# v0.net
KiCad netlist of a schematic drawn in Altium Designer
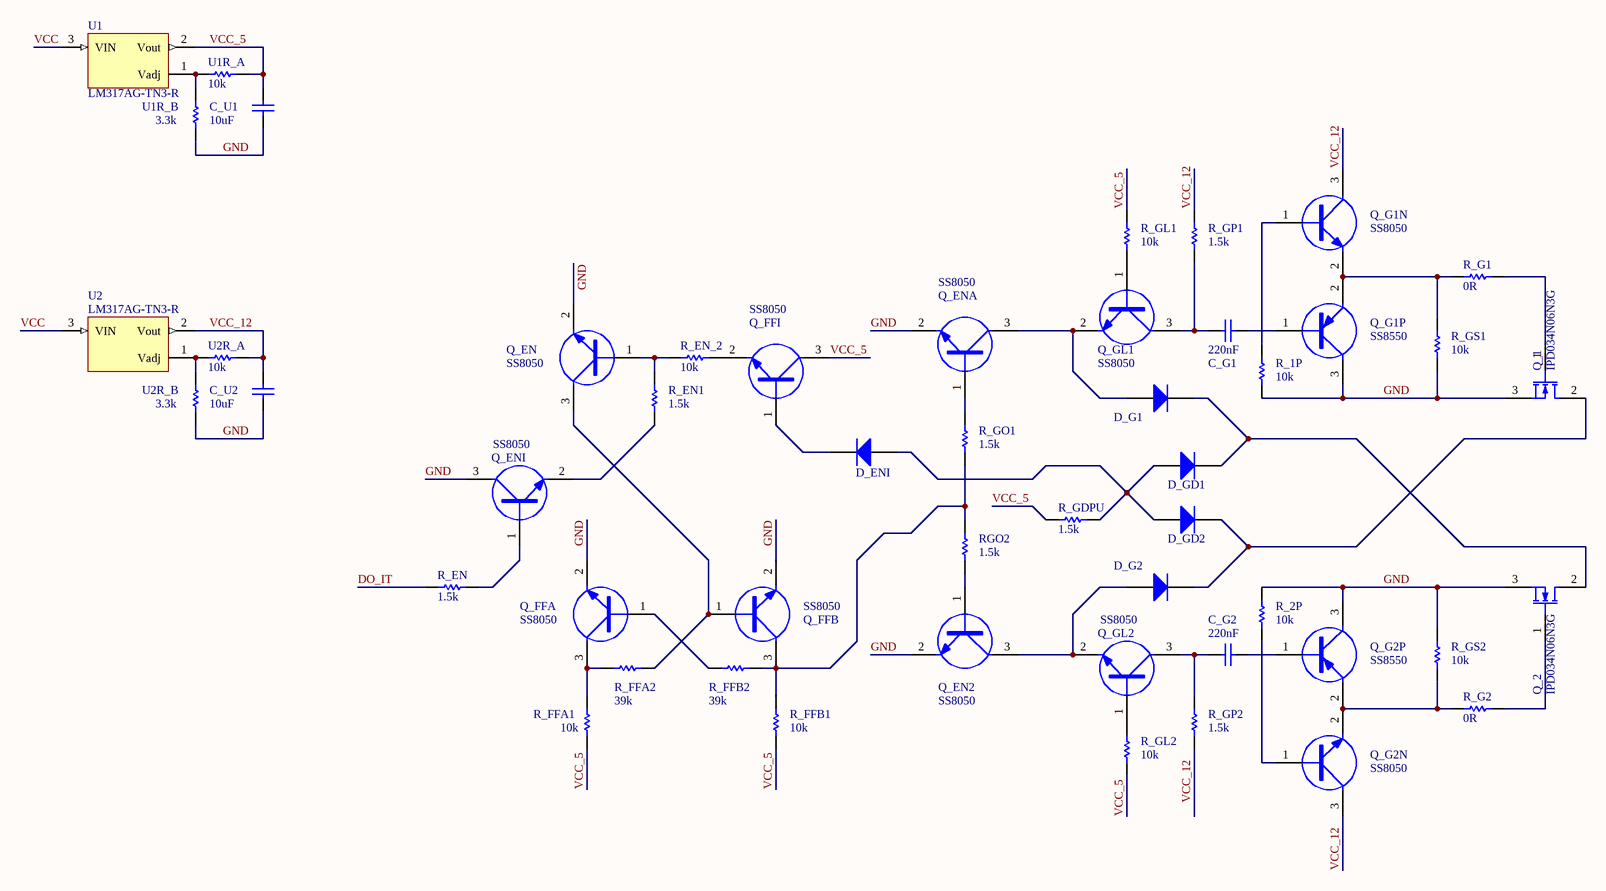
[diagram p0: v0.SchDoc]

(export (version "E")
  (design (tool "Eeschema 10.0.6"))
  (components
    (comp (ref "C_G1")
      (value "220nF")
      (footprint "CAP 0402")
      (description "CAPACITOR MLCC - 220nF 16V 0402")
      (fields (field (name "LCSC PART #") "C16772") (field (name "Comment") "CL05B224KO5NNNC"))
      (libsource (lib "JLC_PCB") (part "CL05B224KO5NNNC"))
    )
    (comp (ref "C_G2")
      (value "220nF")
      (footprint "CAP 0402")
      (description "CAPACITOR MLCC - 220nF 16V 0402")
      (fields (field (name "LCSC PART #") "C16772") (field (name "Comment") "CL05B224KO5NNNC"))
      (libsource (lib "JLC_PCB") (part "CL05B224KO5NNNC"))
    )
    (comp (ref "C_U1")
      (value "10uF")
      (footprint "CAP 0805")
      (description "CAPACITOR MLCC - 10uF 25V 0805")
      (fields (field (name "LCSC PART #") "C15850") (field (name "Comment") "CL21A106KAYNNNE"))
      (libsource (lib "JLC_PCB") (part "CL21A106KAYNNNE"))
    )
    (comp (ref "C_U2")
      (value "10uF")
      (footprint "CAP 0805")
      (description "CAPACITOR MLCC - 10uF 25V 0805")
      (fields (field (name "LCSC PART #") "C15850") (field (name "Comment") "CL21A106KAYNNNE"))
      (libsource (lib "JLC_PCB") (part "CL21A106KAYNNNE"))
    )
    (comp (ref "D_ENI")
      (value "N4148WS")
      (footprint "sod-323")
      (description "DIODE - 100V 150MA 1.25V @ 150MA 4NS SOD-323")
      (fields (field (name "LCSC PART #") "C2128"))
      (libsource (lib "JLC_PCB") (part "N4148WS"))
    )
    (comp (ref "D_G1")
      (value "N4148WS")
      (footprint "sod-323")
      (description "DIODE - 100V 150MA 1.25V @ 150MA 4NS SOD-323")
      (fields (field (name "LCSC PART #") "C2128"))
      (libsource (lib "JLC_PCB") (part "N4148WS"))
    )
    (comp (ref "D_G2")
      (value "N4148WS")
      (footprint "sod-323")
      (description "DIODE - 100V 150MA 1.25V @ 150MA 4NS SOD-323")
      (fields (field (name "LCSC PART #") "C2128"))
      (libsource (lib "JLC_PCB") (part "N4148WS"))
    )
    (comp (ref "D_GD1")
      (value "N4148WS")
      (footprint "sod-323")
      (description "DIODE - 100V 150MA 1.25V @ 150MA 4NS SOD-323")
      (fields (field (name "LCSC PART #") "C2128"))
      (libsource (lib "JLC_PCB") (part "N4148WS"))
    )
    (comp (ref "D_GD2")
      (value "N4148WS")
      (footprint "sod-323")
      (description "DIODE - 100V 150MA 1.25V @ 150MA 4NS SOD-323")
      (fields (field (name "LCSC PART #") "C2128"))
      (libsource (lib "JLC_PCB") (part "N4148WS"))
    )
    (comp (ref "Q_1")
      (value "IPD034N06N3G")
      (footprint "to-252-2")
      (description "MOSFET (N) - TRENCH 60V 100A 4V @ 93UA 3.4 M? @ 100A,10V TO-252-2(DPAK) ROHS")
      (fields (field (name "LCSC PART #") "C94897"))
      (libsource (lib "JLC_PCB") (part "IPD034N06N3G"))
    )
    (comp (ref "Q_2")
      (value "IPD034N06N3G")
      (footprint "to-252-2")
      (description "MOSFET (N) - TRENCH 60V 100A 4V @ 93UA 3.4 M? @ 100A,10V TO-252-2(DPAK) ROHS")
      (fields (field (name "LCSC PART #") "C94897"))
      (libsource (lib "JLC_PCB") (part "IPD034N06N3G"))
    )
    (comp (ref "Q_EN")
      (value "SS8050")
      (footprint "SOT-23-3")
      (description "BJT NPN - 25V 1.5A")
      (fields (field (name "LCSC PART #") "C2150"))
      (libsource (lib "JLC_PCB") (part "SS8050"))
    )
    (comp (ref "Q_EN2")
      (value "SS8050")
      (footprint "SOT-23-3")
      (description "BJT NPN - 25V 1.5A")
      (fields (field (name "LCSC PART #") "C2150"))
      (libsource (lib "JLC_PCB") (part "SS8050"))
    )
    (comp (ref "Q_ENA")
      (value "SS8050")
      (footprint "SOT-23-3")
      (description "BJT NPN - 25V 1.5A")
      (fields (field (name "LCSC PART #") "C2150"))
      (libsource (lib "JLC_PCB") (part "SS8050"))
    )
    (comp (ref "Q_ENI")
      (value "SS8050")
      (footprint "SOT-23-3")
      (description "BJT NPN - 25V 1.5A")
      (fields (field (name "LCSC PART #") "C2150"))
      (libsource (lib "JLC_PCB") (part "SS8050"))
    )
    (comp (ref "Q_FFA")
      (value "SS8050")
      (footprint "SOT-23-3")
      (description "BJT NPN - 25V 1.5A")
      (fields (field (name "LCSC PART #") "C2150"))
      (libsource (lib "JLC_PCB") (part "SS8050"))
    )
    (comp (ref "Q_FFB")
      (value "SS8050")
      (footprint "SOT-23-3")
      (description "BJT NPN - 25V 1.5A")
      (fields (field (name "LCSC PART #") "C2150"))
      (libsource (lib "JLC_PCB") (part "SS8050"))
    )
    (comp (ref "Q_FFI")
      (value "SS8050")
      (footprint "SOT-23-3")
      (description "BJT NPN - 25V 1.5A")
      (fields (field (name "LCSC PART #") "C2150"))
      (libsource (lib "JLC_PCB") (part "SS8050"))
    )
    (comp (ref "Q_G1N")
      (value "SS8050")
      (footprint "SOT-23-3")
      (description "BJT NPN - 25V 1.5A")
      (fields (field (name "LCSC PART #") "C2150"))
      (libsource (lib "JLC_PCB") (part "SS8050"))
    )
    (comp (ref "Q_G1P")
      (value "SS8550")
      (footprint "SOT-23-3")
      (description "BJT PNP - 25V 1.5A")
      (fields (field (name "LCSC PART #") "C8542"))
      (libsource (lib "JLC_PCB") (part "SS8550"))
    )
    (comp (ref "Q_G2N")
      (value "SS8050")
      (footprint "SOT-23-3")
      (description "BJT NPN - 25V 1.5A")
      (fields (field (name "LCSC PART #") "C2150"))
      (libsource (lib "JLC_PCB") (part "SS8050"))
    )
    (comp (ref "Q_G2P")
      (value "SS8550")
      (footprint "SOT-23-3")
      (description "BJT PNP - 25V 1.5A")
      (fields (field (name "LCSC PART #") "C8542"))
      (libsource (lib "JLC_PCB") (part "SS8550"))
    )
    (comp (ref "Q_GL1")
      (value "SS8050")
      (footprint "SOT-23-3")
      (description "BJT NPN - 25V 1.5A")
      (fields (field (name "LCSC PART #") "C2150"))
      (libsource (lib "JLC_PCB") (part "SS8050"))
    )
    (comp (ref "Q_GL2")
      (value "SS8050")
      (footprint "SOT-23-3")
      (description "BJT NPN - 25V 1.5A")
      (fields (field (name "LCSC PART #") "C2150"))
      (libsource (lib "JLC_PCB") (part "SS8050"))
    )
    (comp (ref "RGO2")
      (value "1.5k")
      (footprint "RES 0402")
      (description "RESISTOR SMD - 1.5k 1% 0402")
      (fields (field (name "LCSC PART #") "C25867") (field (name "Comment") "0402WGF1501TCE"))
      (libsource (lib "JLC_PCB") (part "0402WGF1501TCE"))
    )
    (comp (ref "R_1P")
      (value "10k")
      (footprint "RES 0402")
      (description "RESISTOR SMD - 10k 1% 0402")
      (fields (field (name "LCSC PART #") "C25744") (field (name "Comment") "0402WGF1002TCE"))
      (libsource (lib "JLC_PCB") (part "0402WGF1002TCE"))
    )
    (comp (ref "R_2P")
      (value "10k")
      (footprint "RES 0402")
      (description "RESISTOR SMD - 10k 1% 0402")
      (fields (field (name "LCSC PART #") "C25744") (field (name "Comment") "0402WGF1002TCE"))
      (libsource (lib "JLC_PCB") (part "0402WGF1002TCE"))
    )
    (comp (ref "R_EN")
      (value "1.5k")
      (footprint "RES 0402")
      (description "RESISTOR SMD - 1.5k 1% 0402")
      (fields (field (name "LCSC PART #") "C25867") (field (name "Comment") "0402WGF1501TCE"))
      (libsource (lib "JLC_PCB") (part "0402WGF1501TCE"))
    )
    (comp (ref "R_EN1")
      (value "1.5k")
      (footprint "RES 0402")
      (description "RESISTOR SMD - 1.5k 1% 0402")
      (fields (field (name "LCSC PART #") "C25867") (field (name "Comment") "0402WGF1501TCE"))
      (libsource (lib "JLC_PCB") (part "0402WGF1501TCE"))
    )
    (comp (ref "R_EN_2")
      (value "10k")
      (footprint "RES 0402")
      (description "RESISTOR SMD - 10k 1% 0402")
      (fields (field (name "LCSC PART #") "C25744") (field (name "Comment") "0402WGF1002TCE"))
      (libsource (lib "JLC_PCB") (part "0402WGF1002TCE"))
    )
    (comp (ref "R_FFA1")
      (value "10k")
      (footprint "RES 0402")
      (description "RESISTOR SMD - 10k 1% 0402")
      (fields (field (name "LCSC PART #") "C25744") (field (name "Comment") "0402WGF1002TCE"))
      (libsource (lib "JLC_PCB") (part "0402WGF1002TCE"))
    )
    (comp (ref "R_FFA2")
      (value "39k")
      (footprint "RES 0402")
      (description "RESISTOR SMD - 39k 1% 0402")
      (fields (field (name "LCSC PART #") "C25783") (field (name "Comment") "0402WGF3902TCE"))
      (libsource (lib "JLC_PCB") (part "0402WGF3902TCE"))
    )
    (comp (ref "R_FFB1")
      (value "10k")
      (footprint "RES 0402")
      (description "RESISTOR SMD - 10k 1% 0402")
      (fields (field (name "LCSC PART #") "C25744") (field (name "Comment") "0402WGF1002TCE"))
      (libsource (lib "JLC_PCB") (part "0402WGF1002TCE"))
    )
    (comp (ref "R_FFB2")
      (value "39k")
      (footprint "RES 0402")
      (description "RESISTOR SMD - 39k 1% 0402")
      (fields (field (name "LCSC PART #") "C25783") (field (name "Comment") "0402WGF3902TCE"))
      (libsource (lib "JLC_PCB") (part "0402WGF3902TCE"))
    )
    (comp (ref "R_G1")
      (value "0R")
      (footprint "RES 0402")
      (description "RESISTOR SMD - 0R 1% 0402")
      (fields (field (name "LCSC PART #") "C17168") (field (name "Comment") "0402WGF0000TCE"))
      (libsource (lib "JLC_PCB") (part "0402WGF0000TCE"))
    )
    (comp (ref "R_G2")
      (value "0R")
      (footprint "RES 0402")
      (description "RESISTOR SMD - 0R 1% 0402")
      (fields (field (name "LCSC PART #") "C17168") (field (name "Comment") "0402WGF0000TCE"))
      (libsource (lib "JLC_PCB") (part "0402WGF0000TCE"))
    )
    (comp (ref "R_GDPU")
      (value "1.5k")
      (footprint "RES 0402")
      (description "RESISTOR SMD - 1.5k 1% 0402")
      (fields (field (name "LCSC PART #") "C25867") (field (name "Comment") "0402WGF1501TCE"))
      (libsource (lib "JLC_PCB") (part "0402WGF1501TCE"))
    )
    (comp (ref "R_GL1")
      (value "10k")
      (footprint "RES 0402")
      (description "RESISTOR SMD - 10k 1% 0402")
      (fields (field (name "LCSC PART #") "C25744") (field (name "Comment") "0402WGF1002TCE"))
      (libsource (lib "JLC_PCB") (part "0402WGF1002TCE"))
    )
    (comp (ref "R_GL2")
      (value "10k")
      (footprint "RES 0402")
      (description "RESISTOR SMD - 10k 1% 0402")
      (fields (field (name "LCSC PART #") "C25744") (field (name "Comment") "0402WGF1002TCE"))
      (libsource (lib "JLC_PCB") (part "0402WGF1002TCE"))
    )
    (comp (ref "R_GO1")
      (value "1.5k")
      (footprint "RES 0402")
      (description "RESISTOR SMD - 1.5k 1% 0402")
      (fields (field (name "LCSC PART #") "C25867") (field (name "Comment") "0402WGF1501TCE"))
      (libsource (lib "JLC_PCB") (part "0402WGF1501TCE"))
    )
    (comp (ref "R_GP1")
      (value "1.5k")
      (footprint "RES 0402")
      (description "RESISTOR SMD - 1.5k 1% 0402")
      (fields (field (name "LCSC PART #") "C25867") (field (name "Comment") "0402WGF1501TCE"))
      (libsource (lib "JLC_PCB") (part "0402WGF1501TCE"))
    )
    (comp (ref "R_GP2")
      (value "1.5k")
      (footprint "RES 0402")
      (description "RESISTOR SMD - 1.5k 1% 0402")
      (fields (field (name "LCSC PART #") "C25867") (field (name "Comment") "0402WGF1501TCE"))
      (libsource (lib "JLC_PCB") (part "0402WGF1501TCE"))
    )
    (comp (ref "R_GS1")
      (value "10k")
      (footprint "RES 0402")
      (description "RESISTOR SMD - 10k 1% 0402")
      (fields (field (name "LCSC PART #") "C25744") (field (name "Comment") "0402WGF1002TCE"))
      (libsource (lib "JLC_PCB") (part "0402WGF1002TCE"))
    )
    (comp (ref "R_GS2")
      (value "10k")
      (footprint "RES 0402")
      (description "RESISTOR SMD - 10k 1% 0402")
      (fields (field (name "LCSC PART #") "C25744") (field (name "Comment") "0402WGF1002TCE"))
      (libsource (lib "JLC_PCB") (part "0402WGF1002TCE"))
    )
    (comp (ref "U1")
      (value "LM317AG-TN3-R")
      (footprint "TO-252-2")
      (description "IC - LDO")
      (fields (field (name "LCSC PART #") "C75510"))
      (libsource (lib "JLC_PCB") (part "LM317AG-TN3-R"))
    )
    (comp (ref "U1R_A")
      (value "10k")
      (footprint "RES 0402")
      (description "RESISTOR SMD - 10k 1% 0402")
      (fields (field (name "LCSC PART #") "C25744") (field (name "Comment") "0402WGF1002TCE"))
      (libsource (lib "JLC_PCB") (part "0402WGF1002TCE"))
    )
    (comp (ref "U1R_B")
      (value "3.3k")
      (footprint "RES 0402")
      (description "RESISTOR SMD - 3.3k 1% 0402")
      (fields (field (name "LCSC PART #") "C25890") (field (name "Comment") "0402WGF3301TCE"))
      (libsource (lib "JLC_PCB") (part "0402WGF3301TCE"))
    )
    (comp (ref "U2")
      (value "LM317AG-TN3-R")
      (footprint "TO-252-2")
      (description "IC - LDO")
      (fields (field (name "LCSC PART #") "C75510"))
      (libsource (lib "JLC_PCB") (part "LM317AG-TN3-R"))
    )
    (comp (ref "U2R_A")
      (value "10k")
      (footprint "RES 0402")
      (description "RESISTOR SMD - 10k 1% 0402")
      (fields (field (name "LCSC PART #") "C25744") (field (name "Comment") "0402WGF1002TCE"))
      (libsource (lib "JLC_PCB") (part "0402WGF1002TCE"))
    )
    (comp (ref "U2R_B")
      (value "3.3k")
      (footprint "RES 0402")
      (description "RESISTOR SMD - 3.3k 1% 0402")
      (fields (field (name "LCSC PART #") "C25890") (field (name "Comment") "0402WGF3301TCE"))
      (libsource (lib "JLC_PCB") (part "0402WGF3301TCE"))
    )
  )
  (nets
    (net (code "1") (name "/DO_IT") (class "Default")
      (node (ref "R_EN") (pin "2") (pinfunction "2_2") (pintype "passive"))
    )
    (net (code "2") (name "/GND") (class "Default")
      (node (ref "C_U1") (pin "1") (pinfunction "1_1") (pintype "passive"))
      (node (ref "C_U2") (pin "1") (pinfunction "1_1") (pintype "passive"))
      (node (ref "Q_1") (pin "3") (pinfunction "S_3") (pintype "passive"))
      (node (ref "Q_2") (pin "3") (pinfunction "S_3") (pintype "passive"))
      (node (ref "Q_EN") (pin "2") (pinfunction "E_2") (pintype "passive"))
      (node (ref "Q_EN2") (pin "2") (pinfunction "E_2") (pintype "passive"))
      (node (ref "Q_ENA") (pin "2") (pinfunction "E_2") (pintype "passive"))
      (node (ref "Q_ENI") (pin "3") (pinfunction "C_3") (pintype "passive"))
      (node (ref "Q_FFA") (pin "2") (pinfunction "E_2") (pintype "passive"))
      (node (ref "Q_FFB") (pin "2") (pinfunction "E_2") (pintype "passive"))
      (node (ref "Q_G1P") (pin "3") (pinfunction "C_3") (pintype "passive"))
      (node (ref "Q_G2P") (pin "3") (pinfunction "C_3") (pintype "passive"))
      (node (ref "R_1P") (pin "1") (pinfunction "1_1") (pintype "passive"))
      (node (ref "R_2P") (pin "2") (pinfunction "2_2") (pintype "passive"))
      (node (ref "R_GS1") (pin "1") (pinfunction "1_1") (pintype "passive"))
      (node (ref "R_GS2") (pin "2") (pinfunction "2_2") (pintype "passive"))
      (node (ref "U1R_B") (pin "1") (pinfunction "1_1") (pintype "passive"))
      (node (ref "U2R_B") (pin "1") (pinfunction "1_1") (pintype "passive"))
    )
    (net (code "3") (name "/VCC") (class "Default")
      (node (ref "U1") (pin "3") (pinfunction "VIN_3") (pintype "input"))
      (node (ref "U2") (pin "3") (pinfunction "VIN_3") (pintype "input"))
    )
    (net (code "4") (name "/VCC_5") (class "Default")
      (node (ref "C_U1") (pin "2") (pinfunction "2_2") (pintype "passive"))
      (node (ref "Q_FFI") (pin "3") (pinfunction "C_3") (pintype "passive"))
      (node (ref "R_FFA1") (pin "2") (pinfunction "2_2") (pintype "passive"))
      (node (ref "R_FFB1") (pin "2") (pinfunction "2_2") (pintype "passive"))
      (node (ref "R_GDPU") (pin "2") (pinfunction "2_2") (pintype "passive"))
      (node (ref "R_GL1") (pin "2") (pinfunction "2_2") (pintype "passive"))
      (node (ref "R_GL2") (pin "1") (pinfunction "1_1") (pintype "passive"))
      (node (ref "U1") (pin "2") (pinfunction "Vout_2") (pintype "output"))
      (node (ref "U1R_A") (pin "1") (pinfunction "1_1") (pintype "passive"))
    )
    (net (code "5") (name "/VCC_12") (class "Default")
      (node (ref "C_U2") (pin "2") (pinfunction "2_2") (pintype "passive"))
      (node (ref "Q_G1N") (pin "3") (pinfunction "C_3") (pintype "passive"))
      (node (ref "Q_G2N") (pin "3") (pinfunction "C_3") (pintype "passive"))
      (node (ref "R_GP1") (pin "2") (pinfunction "2_2") (pintype "passive"))
      (node (ref "R_GP2") (pin "1") (pinfunction "1_1") (pintype "passive"))
      (node (ref "U2") (pin "2") (pinfunction "Vout_2") (pintype "output"))
      (node (ref "U2R_A") (pin "1") (pinfunction "1_1") (pintype "passive"))
    )
    (net (code "6") (name "Net-(D_ENI-A)") (class "Default")
      (node (ref "D_ENI") (pin "2") (pinfunction "A_2") (pintype "passive"))
      (node (ref "D_GD1") (pin "2") (pinfunction "A_2") (pintype "passive"))
      (node (ref "D_GD2") (pin "2") (pinfunction "A_2") (pintype "passive"))
      (node (ref "R_GDPU") (pin "1") (pinfunction "1_1") (pintype "passive"))
    )
    (net (code "7") (name "Net-(D_ENI-K)") (class "Default")
      (node (ref "D_ENI") (pin "1") (pinfunction "K_1") (pintype "passive"))
      (node (ref "Q_FFI") (pin "1") (pinfunction "B_1") (pintype "passive"))
    )
    (net (code "8") (name "Net-(D_G1-A)") (class "Default")
      (node (ref "D_G1") (pin "2") (pinfunction "A_2") (pintype "passive"))
      (node (ref "Q_ENA") (pin "3") (pinfunction "C_3") (pintype "passive"))
      (node (ref "Q_GL1") (pin "2") (pinfunction "E_2") (pintype "passive"))
    )
    (net (code "9") (name "Net-(D_G1-K)") (class "Default")
      (node (ref "D_G1") (pin "1") (pinfunction "K_1") (pintype "passive"))
      (node (ref "D_GD1") (pin "1") (pinfunction "K_1") (pintype "passive"))
      (node (ref "Q_2") (pin "2") (pinfunction "D_2") (pintype "passive"))
    )
    (net (code "10") (name "Net-(D_G2-A)") (class "Default")
      (node (ref "D_G2") (pin "2") (pinfunction "A_2") (pintype "passive"))
      (node (ref "Q_EN2") (pin "3") (pinfunction "C_3") (pintype "passive"))
      (node (ref "Q_GL2") (pin "2") (pinfunction "E_2") (pintype "passive"))
    )
    (net (code "11") (name "Net-(D_G2-K)") (class "Default")
      (node (ref "D_G2") (pin "1") (pinfunction "K_1") (pintype "passive"))
      (node (ref "D_GD2") (pin "1") (pinfunction "K_1") (pintype "passive"))
      (node (ref "Q_1") (pin "2") (pinfunction "D_2") (pintype "passive"))
    )
    (net (code "12") (name "Net-(Q_1-G)") (class "Default")
      (node (ref "Q_1") (pin "1") (pinfunction "G_1") (pintype "passive"))
      (node (ref "R_G1") (pin "2") (pinfunction "2_2") (pintype "passive"))
    )
    (net (code "13") (name "Net-(Q_2-G)") (class "Default")
      (node (ref "Q_2") (pin "1") (pinfunction "G_1") (pintype "passive"))
      (node (ref "R_G2") (pin "2") (pinfunction "2_2") (pintype "passive"))
    )
    (net (code "14") (name "Net-(Q_EN-B)") (class "Default")
      (node (ref "Q_EN") (pin "1") (pinfunction "B_1") (pintype "passive"))
      (node (ref "R_EN1") (pin "2") (pinfunction "2_2") (pintype "passive"))
      (node (ref "R_EN_2") (pin "2") (pinfunction "2_2") (pintype "passive"))
    )
    (net (code "15") (name "Net-(Q_EN-C)") (class "Default")
      (node (ref "Q_EN") (pin "3") (pinfunction "C_3") (pintype "passive"))
      (node (ref "Q_FFB") (pin "1") (pinfunction "B_1") (pintype "passive"))
      (node (ref "R_FFA2") (pin "2") (pinfunction "2_2") (pintype "passive"))
    )
    (net (code "16") (name "Net-(Q_EN2-B)") (class "Default")
      (node (ref "Q_EN2") (pin "1") (pinfunction "B_1") (pintype "passive"))
      (node (ref "RGO2") (pin "1") (pinfunction "1_1") (pintype "passive"))
    )
    (net (code "17") (name "Net-(Q_ENA-B)") (class "Default")
      (node (ref "Q_ENA") (pin "1") (pinfunction "B_1") (pintype "passive"))
      (node (ref "R_GO1") (pin "2") (pinfunction "2_2") (pintype "passive"))
    )
    (net (code "18") (name "Net-(Q_ENI-B)") (class "Default")
      (node (ref "Q_ENI") (pin "1") (pinfunction "B_1") (pintype "passive"))
      (node (ref "R_EN") (pin "1") (pinfunction "1_1") (pintype "passive"))
    )
    (net (code "19") (name "Net-(Q_ENI-E)") (class "Default")
      (node (ref "Q_ENI") (pin "2") (pinfunction "E_2") (pintype "passive"))
      (node (ref "R_EN1") (pin "1") (pinfunction "1_1") (pintype "passive"))
    )
    (net (code "20") (name "Net-(Q_FFA-B)") (class "Default")
      (node (ref "Q_FFA") (pin "1") (pinfunction "B_1") (pintype "passive"))
      (node (ref "R_FFB2") (pin "1") (pinfunction "1_1") (pintype "passive"))
    )
    (net (code "21") (name "Net-(Q_FFA-C)") (class "Default")
      (node (ref "Q_FFA") (pin "3") (pinfunction "C_3") (pintype "passive"))
      (node (ref "R_FFA1") (pin "1") (pinfunction "1_1") (pintype "passive"))
      (node (ref "R_FFA2") (pin "1") (pinfunction "1_1") (pintype "passive"))
    )
    (net (code "22") (name "Net-(Q_FFB-C)") (class "Default")
      (node (ref "Q_FFB") (pin "3") (pinfunction "C_3") (pintype "passive"))
      (node (ref "RGO2") (pin "2") (pinfunction "2_2") (pintype "passive"))
      (node (ref "R_FFB1") (pin "1") (pinfunction "1_1") (pintype "passive"))
      (node (ref "R_FFB2") (pin "2") (pinfunction "2_2") (pintype "passive"))
      (node (ref "R_GO1") (pin "1") (pinfunction "1_1") (pintype "passive"))
    )
    (net (code "23") (name "Net-(Q_FFI-E)") (class "Default")
      (node (ref "Q_FFI") (pin "2") (pinfunction "E_2") (pintype "passive"))
      (node (ref "R_EN_2") (pin "1") (pinfunction "1_1") (pintype "passive"))
    )
    (net (code "24") (name "Net-(Q_G1N-B)") (class "Default")
      (node (ref "Q_G1N") (pin "1") (pinfunction "B_1") (pintype "passive"))
      (node (ref "R_1P") (pin "2") (pinfunction "2_2") (pintype "passive"))
    )
    (net (code "25") (name "Net-(Q_G1N-E)") (class "Default")
      (node (ref "Q_G1N") (pin "2") (pinfunction "E_2") (pintype "passive"))
      (node (ref "Q_G1P") (pin "2") (pinfunction "E_2") (pintype "passive"))
      (node (ref "R_G1") (pin "1") (pinfunction "1_1") (pintype "passive"))
      (node (ref "R_GS1") (pin "2") (pinfunction "2_2") (pintype "passive"))
    )
    (net (code "26") (name "Net-(Q_G1P-B)") (class "Default")
      (node (ref "C_G1") (pin "2") (pinfunction "2_2") (pintype "passive"))
      (node (ref "Q_G1P") (pin "1") (pinfunction "B_1") (pintype "passive"))
    )
    (net (code "27") (name "Net-(Q_G2N-B)") (class "Default")
      (node (ref "Q_G2N") (pin "1") (pinfunction "B_1") (pintype "passive"))
      (node (ref "R_2P") (pin "1") (pinfunction "1_1") (pintype "passive"))
    )
    (net (code "28") (name "Net-(Q_G2N-E)") (class "Default")
      (node (ref "Q_G2N") (pin "2") (pinfunction "E_2") (pintype "passive"))
      (node (ref "Q_G2P") (pin "2") (pinfunction "E_2") (pintype "passive"))
      (node (ref "R_G2") (pin "1") (pinfunction "1_1") (pintype "passive"))
      (node (ref "R_GS2") (pin "1") (pinfunction "1_1") (pintype "passive"))
    )
    (net (code "29") (name "Net-(Q_G2P-B)") (class "Default")
      (node (ref "C_G2") (pin "2") (pinfunction "2_2") (pintype "passive"))
      (node (ref "Q_G2P") (pin "1") (pinfunction "B_1") (pintype "passive"))
    )
    (net (code "30") (name "Net-(Q_GL1-B)") (class "Default")
      (node (ref "Q_GL1") (pin "1") (pinfunction "B_1") (pintype "passive"))
      (node (ref "R_GL1") (pin "1") (pinfunction "1_1") (pintype "passive"))
    )
    (net (code "31") (name "Net-(Q_GL1-C)") (class "Default")
      (node (ref "C_G1") (pin "1") (pinfunction "1_1") (pintype "passive"))
      (node (ref "Q_GL1") (pin "3") (pinfunction "C_3") (pintype "passive"))
      (node (ref "R_GP1") (pin "1") (pinfunction "1_1") (pintype "passive"))
    )
    (net (code "32") (name "Net-(Q_GL2-B)") (class "Default")
      (node (ref "Q_GL2") (pin "1") (pinfunction "B_1") (pintype "passive"))
      (node (ref "R_GL2") (pin "2") (pinfunction "2_2") (pintype "passive"))
    )
    (net (code "33") (name "Net-(Q_GL2-C)") (class "Default")
      (node (ref "C_G2") (pin "1") (pinfunction "1_1") (pintype "passive"))
      (node (ref "Q_GL2") (pin "3") (pinfunction "C_3") (pintype "passive"))
      (node (ref "R_GP2") (pin "2") (pinfunction "2_2") (pintype "passive"))
    )
    (net (code "34") (name "Net-(U1-Vadj)") (class "Default")
      (node (ref "U1") (pin "1") (pinfunction "Vadj_1") (pintype "power_in"))
      (node (ref "U1R_A") (pin "2") (pinfunction "2_2") (pintype "passive"))
      (node (ref "U1R_B") (pin "2") (pinfunction "2_2") (pintype "passive"))
    )
    (net (code "35") (name "Net-(U2-Vadj)") (class "Default")
      (node (ref "U2") (pin "1") (pinfunction "Vadj_1") (pintype "power_in"))
      (node (ref "U2R_A") (pin "2") (pinfunction "2_2") (pintype "passive"))
      (node (ref "U2R_B") (pin "2") (pinfunction "2_2") (pintype "passive"))
    )
  )
)
